# board_0_5v.net
KiCad netlist of a schematic drawn in EAGLE
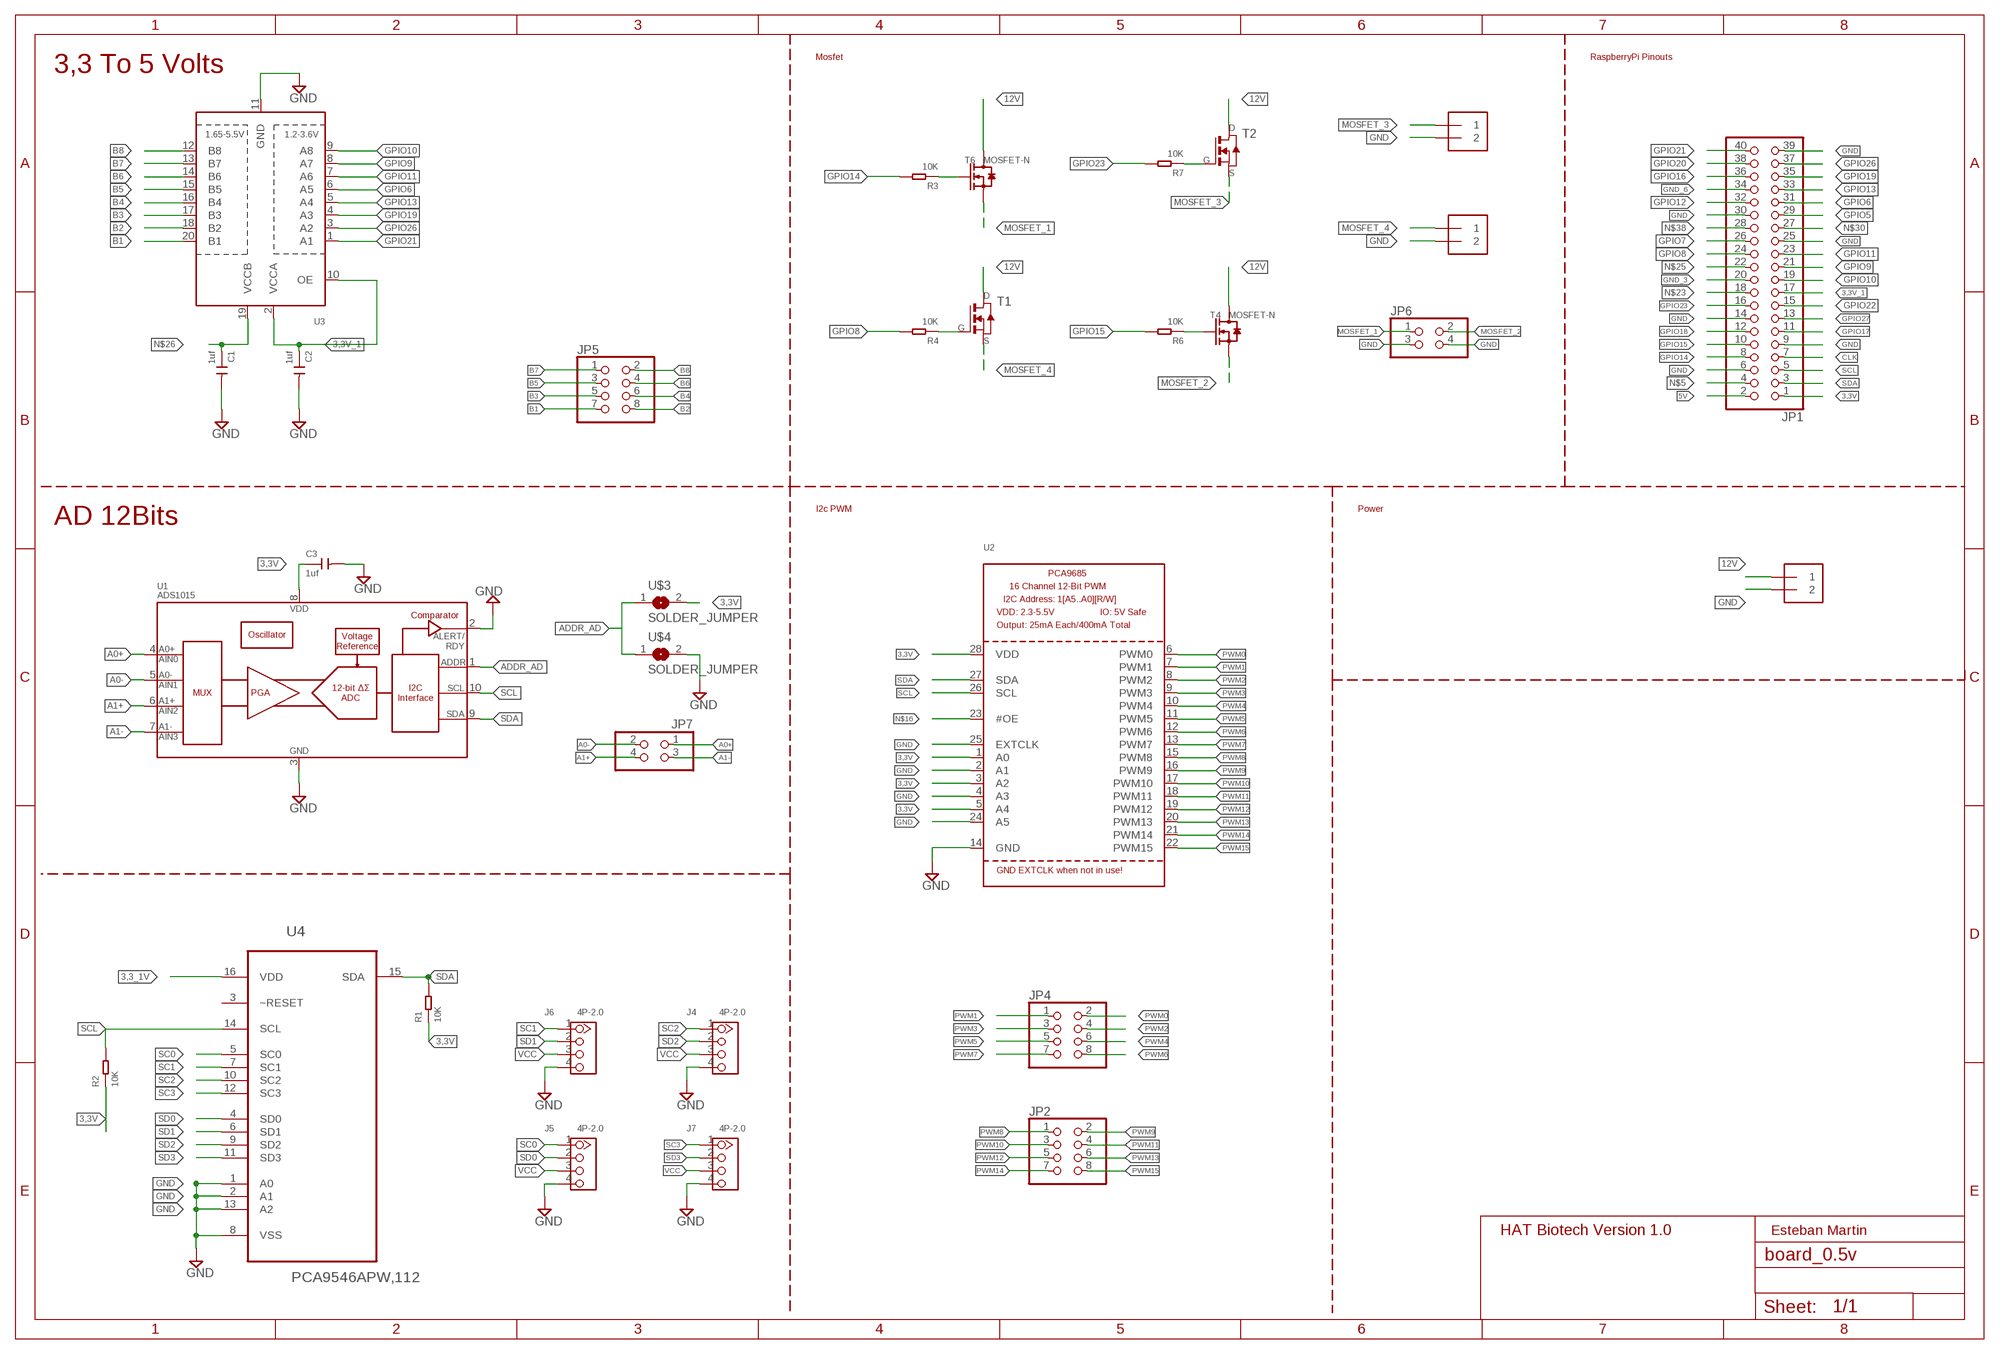
[diagram p0: schematic, sheet 1]

(export (version "E")
  (design (tool "Eeschema 10.0.6"))
  (components
    (comp (ref "C1")
      (value "1uf")
      (footprint "eagle-import:C0805")
      (fields (field (name "MPN") "CC0805KKX7R8BB105"))
      (libsource (lib "eagle-import") (part "CERAMIC-1UF-25V-10%-X7R(0805)"))
    )
    (comp (ref "C2")
      (value "1uf")
      (footprint "eagle-import:C0805")
      (fields (field (name "MPN") "CC0805KKX7R8BB105"))
      (libsource (lib "eagle-import") (part "CERAMIC-1UF-25V-10%-X7R(0805)"))
    )
    (comp (ref "C3")
      (value "1uf")
      (footprint "eagle-import:C0805")
      (fields (field (name "MPN") "CC0805KKX7R8BB105"))
      (libsource (lib "eagle-import") (part "CERAMIC-1UF-25V-10%-X7R(0805)"))
    )
    (comp (ref "J1")
      (value "1X2-3.5MM")
      (footprint "eagle-import:1X2-3.5MM")
      (libsource (lib "eagle-import") (part "1X2-3.5MM"))
    )
    (comp (ref "J2")
      (value "1X2-3.5MM")
      (footprint "eagle-import:1X2-3.5MM")
      (libsource (lib "eagle-import") (part "1X2-3.5MM"))
    )
    (comp (ref "J3")
      (value "1X2-3.5MM")
      (footprint "eagle-import:1X2-3.5MM")
      (libsource (lib "eagle-import") (part "1X2-3.5MM"))
    )
    (comp (ref "J4")
      (value "4P-2.0")
      (footprint "eagle-import:HW4-2.0")
      (libsource (lib "eagle-import") (part "GROVE-CONNECTOR-DIP(4P-2.0)"))
    )
    (comp (ref "J5")
      (value "4P-2.0")
      (footprint "eagle-import:HW4-2.0")
      (libsource (lib "eagle-import") (part "GROVE-CONNECTOR-DIP(4P-2.0)"))
    )
    (comp (ref "J6")
      (value "4P-2.0")
      (footprint "eagle-import:HW4-2.0")
      (libsource (lib "eagle-import") (part "GROVE-CONNECTOR-DIP(4P-2.0)"))
    )
    (comp (ref "J7")
      (value "4P-2.0")
      (footprint "eagle-import:HW4-2.0")
      (libsource (lib "eagle-import") (part "GROVE-CONNECTOR-DIP(4P-2.0)"))
    )
    (comp (ref "JP1")
      (value "PINHD-2X20")
      (footprint "eagle-import:2X20")
      (libsource (lib "eagle-import") (part "PINHD-2X20"))
    )
    (comp (ref "JP2")
      (value "PINHD-2X4")
      (footprint "eagle-import:2X04")
      (libsource (lib "eagle-import") (part "PINHD-2X4"))
    )
    (comp (ref "JP4")
      (value "PINHD-2X4")
      (footprint "eagle-import:2X04")
      (libsource (lib "eagle-import") (part "PINHD-2X4"))
    )
    (comp (ref "JP5")
      (value "PINHD-2X4")
      (footprint "eagle-import:2X04")
      (libsource (lib "eagle-import") (part "PINHD-2X4"))
    )
    (comp (ref "JP6")
      (value "PINHD-2X2")
      (footprint "eagle-import:2X02")
      (libsource (lib "eagle-import") (part "PINHD-2X2"))
    )
    (comp (ref "JP7")
      (value "PINHD-2X2")
      (footprint "eagle-import:2X02")
      (libsource (lib "eagle-import") (part "PINHD-2X2"))
    )
    (comp (ref "R1")
      (value "10K")
      (footprint "eagle-import:R0805")
      (fields (field (name "MPN") "RC0805FR-0710KL"))
      (libsource (lib "eagle-import") (part "SMD-RES-10K-1%-1/8W(0805)"))
    )
    (comp (ref "R2")
      (value "10K")
      (footprint "eagle-import:R0805")
      (fields (field (name "MPN") "RC0805FR-0710KL"))
      (libsource (lib "eagle-import") (part "SMD-RES-10K-1%-1/8W(0805)"))
    )
    (comp (ref "R3")
      (value "10K")
      (footprint "eagle-import:R0805")
      (fields (field (name "MPN") "RC0805FR-0710KL"))
      (libsource (lib "eagle-import") (part "SMD-RES-10K-1%-1/8W(0805)"))
    )
    (comp (ref "R4")
      (value "10K")
      (footprint "eagle-import:R0805")
      (fields (field (name "MPN") "RC0805FR-0710KL"))
      (libsource (lib "eagle-import") (part "SMD-RES-10K-1%-1/8W(0805)"))
    )
    (comp (ref "R6")
      (value "10K")
      (footprint "eagle-import:R0805")
      (fields (field (name "MPN") "RC0805FR-0710KL"))
      (libsource (lib "eagle-import") (part "SMD-RES-10K-1%-1/8W(0805)"))
    )
    (comp (ref "R7")
      (value "10K")
      (footprint "eagle-import:R0805")
      (fields (field (name "MPN") "RC0805FR-0710KL"))
      (libsource (lib "eagle-import") (part "SMD-RES-10K-1%-1/8W(0805)"))
    )
    (comp (ref "T1")
      (value "NMOSFETTO252")
      (footprint "eagle-import:TO252")
      (libsource (lib "eagle-import") (part "NMOSFETTO252"))
    )
    (comp (ref "T2")
      (value "NMOSFETTO252")
      (footprint "eagle-import:TO252")
      (libsource (lib "eagle-import") (part "NMOSFETTO252"))
    )
    (comp (ref "T4")
      (value "MOSFET-N")
      (footprint "eagle-import:SOT-23")
      (libsource (lib "eagle-import") (part "MOSFET-N"))
    )
    (comp (ref "T6")
      (value "MOSFET-N")
      (footprint "eagle-import:SOT-23")
      (libsource (lib "eagle-import") (part "MOSFET-N"))
    )
    (comp (ref "U$3")
      (value "SOLDER_JUMPER")
      (footprint "eagle-import:SJFAB")
      (libsource (lib "eagle-import") (part "SOLDER_JUMPER"))
    )
    (comp (ref "U$4")
      (value "SOLDER_JUMPER")
      (footprint "eagle-import:SJFAB")
      (libsource (lib "eagle-import") (part "SOLDER_JUMPER"))
    )
    (comp (ref "U1")
      (value "ADS1015")
      (footprint "eagle-import:MSOP10")
      (libsource (lib "eagle-import") (part "ADS1015"))
    )
    (comp (ref "U2")
      (value "PCA9685")
      (footprint "eagle-import:TSSOP28")
      (libsource (lib "eagle-import") (part "PCA9685"))
    )
    (comp (ref "U3")
      (value "TXB0108PWR")
      (footprint "eagle-import:TSSOP20")
      (libsource (lib "eagle-import") (part "TXB0108PWR"))
    )
    (comp (ref "U4")
      (value "PCA9546APW,112")
      (footprint "eagle-import:SOP65P640X110-16N")
      (libsource (lib "eagle-import") (part "PCA9546APW,112"))
    )
  )
  (nets
    (net (code "1") (name "3,3V") (class "Default")
      (node (ref "C3") (pin "1") (pinfunction "1_1") (pintype "passive"))
      (node (ref "JP1") (pin "1") (pinfunction "1_1") (pintype "passive"))
      (node (ref "R1") (pin "1") (pinfunction "1_1") (pintype "passive"))
      (node (ref "R2") (pin "1") (pinfunction "1_1") (pintype "passive"))
      (node (ref "U$3") (pin "2") (pinfunction "2_2") (pintype "passive"))
      (node (ref "U1") (pin "8") (pinfunction "VDD_8") (pintype "bidirectional"))
      (node (ref "U2") (pin "1") (pinfunction "A0_1") (pintype "bidirectional"))
      (node (ref "U2") (pin "28") (pinfunction "VDD_28") (pintype "power_in"))
      (node (ref "U2") (pin "3") (pinfunction "A2_3") (pintype "bidirectional"))
      (node (ref "U2") (pin "5") (pinfunction "A4_5") (pintype "bidirectional"))
    )
    (net (code "2") (name "3,3V_1") (class "Default")
      (node (ref "C2") (pin "1") (pinfunction "1_1") (pintype "passive"))
      (node (ref "JP1") (pin "17") (pinfunction "17_17") (pintype "passive"))
      (node (ref "U3") (pin "10") (pinfunction "OE_10") (pintype "bidirectional"))
      (node (ref "U3") (pin "2") (pinfunction "VCCA_2") (pintype "bidirectional"))
    )
    (net (code "3") (name "3,3_1V") (class "Default")
      (node (ref "U4") (pin "16") (pinfunction "VDD_16") (pintype "power_in"))
    )
    (net (code "4") (name "5V") (class "Default")
      (node (ref "JP1") (pin "2") (pinfunction "2_2") (pintype "passive"))
    )
    (net (code "5") (name "12V") (class "Default")
      (node (ref "J2") (pin "1") (pinfunction "1_1") (pintype "passive"))
      (node (ref "T1") (pin "3") (pinfunction "D_3") (pintype "passive"))
      (node (ref "T2") (pin "3") (pinfunction "D_3") (pintype "passive"))
      (node (ref "T4") (pin "3") (pinfunction "D_3") (pintype "passive"))
      (node (ref "T6") (pin "3") (pinfunction "D_3") (pintype "passive"))
    )
    (net (code "6") (name "A0+") (class "Default")
      (node (ref "JP7") (pin "1") (pinfunction "1_1") (pintype "passive"))
      (node (ref "U1") (pin "4") (pinfunction "AIN0_4") (pintype "bidirectional"))
    )
    (net (code "7") (name "A0-") (class "Default")
      (node (ref "JP7") (pin "2") (pinfunction "2_2") (pintype "passive"))
      (node (ref "U1") (pin "5") (pinfunction "AIN1_5") (pintype "bidirectional"))
    )
    (net (code "8") (name "A1+") (class "Default")
      (node (ref "JP7") (pin "4") (pinfunction "4_4") (pintype "passive"))
      (node (ref "U1") (pin "6") (pinfunction "AIN2_6") (pintype "bidirectional"))
    )
    (net (code "9") (name "A1-") (class "Default")
      (node (ref "JP7") (pin "3") (pinfunction "3_3") (pintype "passive"))
      (node (ref "U1") (pin "7") (pinfunction "AIN3_7") (pintype "bidirectional"))
    )
    (net (code "10") (name "ADDR_AD") (class "Default")
      (node (ref "U$3") (pin "1") (pinfunction "1_1") (pintype "passive"))
      (node (ref "U$4") (pin "1") (pinfunction "1_1") (pintype "passive"))
      (node (ref "U1") (pin "1") (pinfunction "ADDR_1") (pintype "bidirectional"))
    )
    (net (code "11") (name "B1") (class "Default")
      (node (ref "JP5") (pin "7") (pinfunction "7_7") (pintype "passive"))
      (node (ref "U3") (pin "20") (pinfunction "B1_20") (pintype "bidirectional"))
    )
    (net (code "12") (name "B2") (class "Default")
      (node (ref "JP5") (pin "8") (pinfunction "8_8") (pintype "passive"))
      (node (ref "U3") (pin "18") (pinfunction "B2_18") (pintype "bidirectional"))
    )
    (net (code "13") (name "B3") (class "Default")
      (node (ref "JP5") (pin "5") (pinfunction "5_5") (pintype "passive"))
      (node (ref "U3") (pin "17") (pinfunction "B3_17") (pintype "bidirectional"))
    )
    (net (code "14") (name "B4") (class "Default")
      (node (ref "JP5") (pin "6") (pinfunction "6_6") (pintype "passive"))
      (node (ref "U3") (pin "16") (pinfunction "B4_16") (pintype "bidirectional"))
    )
    (net (code "15") (name "B5") (class "Default")
      (node (ref "JP5") (pin "3") (pinfunction "3_3") (pintype "passive"))
      (node (ref "U3") (pin "15") (pinfunction "B5_15") (pintype "bidirectional"))
    )
    (net (code "16") (name "B6") (class "Default")
      (node (ref "JP5") (pin "4") (pinfunction "4_4") (pintype "passive"))
      (node (ref "U3") (pin "14") (pinfunction "B6_14") (pintype "bidirectional"))
    )
    (net (code "17") (name "B7") (class "Default")
      (node (ref "JP5") (pin "1") (pinfunction "1_1") (pintype "passive"))
      (node (ref "U3") (pin "13") (pinfunction "B7_13") (pintype "bidirectional"))
    )
    (net (code "18") (name "B8") (class "Default")
      (node (ref "JP5") (pin "2") (pinfunction "2_2") (pintype "passive"))
      (node (ref "U3") (pin "12") (pinfunction "B8_12") (pintype "bidirectional"))
    )
    (net (code "19") (name "CLK") (class "Default")
      (node (ref "JP1") (pin "7") (pinfunction "7_7") (pintype "passive"))
    )
    (net (code "20") (name "GND") (class "Default")
      (node (ref "C1") (pin "2") (pinfunction "2_2") (pintype "passive"))
      (node (ref "C2") (pin "2") (pinfunction "2_2") (pintype "passive"))
      (node (ref "C3") (pin "2") (pinfunction "2_2") (pintype "passive"))
      (node (ref "J1") (pin "2") (pinfunction "2_2") (pintype "passive"))
      (node (ref "J2") (pin "2") (pinfunction "2_2") (pintype "passive"))
      (node (ref "J3") (pin "2") (pinfunction "2_2") (pintype "passive"))
      (node (ref "J4") (pin "4") (pinfunction "4_4") (pintype "bidirectional"))
      (node (ref "J5") (pin "4") (pinfunction "4_4") (pintype "bidirectional"))
      (node (ref "J6") (pin "4") (pinfunction "4_4") (pintype "bidirectional"))
      (node (ref "J7") (pin "4") (pinfunction "4_4") (pintype "bidirectional"))
      (node (ref "JP1") (pin "14") (pinfunction "14_14") (pintype "passive"))
      (node (ref "JP1") (pin "25") (pinfunction "25_25") (pintype "passive"))
      (node (ref "JP1") (pin "30") (pinfunction "30_30") (pintype "passive"))
      (node (ref "JP1") (pin "39") (pinfunction "39_39") (pintype "passive"))
      (node (ref "JP1") (pin "6") (pinfunction "6_6") (pintype "passive"))
      (node (ref "JP1") (pin "9") (pinfunction "9_9") (pintype "passive"))
      (node (ref "JP6") (pin "3") (pinfunction "3_3") (pintype "passive"))
      (node (ref "JP6") (pin "4") (pinfunction "4_4") (pintype "passive"))
      (node (ref "U$4") (pin "2") (pinfunction "2_2") (pintype "passive"))
      (node (ref "U1") (pin "2") (pinfunction "ALERT/RDY_2") (pintype "bidirectional"))
      (node (ref "U1") (pin "3") (pinfunction "VSS_3") (pintype "bidirectional"))
      (node (ref "U2") (pin "14") (pinfunction "GND_14") (pintype "power_in"))
      (node (ref "U2") (pin "2") (pinfunction "A1_2") (pintype "bidirectional"))
      (node (ref "U2") (pin "24") (pinfunction "A5_24") (pintype "bidirectional"))
      (node (ref "U2") (pin "25") (pinfunction "EXTCLK_25") (pintype "input"))
      (node (ref "U2") (pin "4") (pinfunction "A3_4") (pintype "bidirectional"))
      (node (ref "U3") (pin "11") (pinfunction "GND_11") (pintype "bidirectional"))
      (node (ref "U4") (pin "1") (pinfunction "A0_1") (pintype "input"))
      (node (ref "U4") (pin "13") (pinfunction "A2_13") (pintype "input"))
      (node (ref "U4") (pin "2") (pinfunction "A1_2") (pintype "input"))
      (node (ref "U4") (pin "8") (pinfunction "VSS_8") (pintype "passive"))
    )
    (net (code "21") (name "GND_3") (class "Default")
      (node (ref "JP1") (pin "20") (pinfunction "20_20") (pintype "passive"))
    )
    (net (code "22") (name "GND_6") (class "Default")
      (node (ref "JP1") (pin "34") (pinfunction "34_34") (pintype "passive"))
    )
    (net (code "23") (name "GPIO5") (class "Default")
      (node (ref "JP1") (pin "29") (pinfunction "29_29") (pintype "passive"))
    )
    (net (code "24") (name "GPIO6") (class "Default")
      (node (ref "JP1") (pin "31") (pinfunction "31_31") (pintype "passive"))
      (node (ref "U3") (pin "6") (pinfunction "A5_6") (pintype "bidirectional"))
    )
    (net (code "25") (name "GPIO7") (class "Default")
      (node (ref "JP1") (pin "26") (pinfunction "26_26") (pintype "passive"))
    )
    (net (code "26") (name "GPIO8") (class "Default")
      (node (ref "JP1") (pin "24") (pinfunction "24_24") (pintype "passive"))
      (node (ref "R4") (pin "2") (pinfunction "2_2") (pintype "passive"))
    )
    (net (code "27") (name "GPIO9") (class "Default")
      (node (ref "JP1") (pin "21") (pinfunction "21_21") (pintype "passive"))
      (node (ref "U3") (pin "8") (pinfunction "A7_8") (pintype "bidirectional"))
    )
    (net (code "28") (name "GPIO10") (class "Default")
      (node (ref "JP1") (pin "19") (pinfunction "19_19") (pintype "passive"))
      (node (ref "U3") (pin "9") (pinfunction "A8_9") (pintype "bidirectional"))
    )
    (net (code "29") (name "GPIO11") (class "Default")
      (node (ref "JP1") (pin "23") (pinfunction "23_23") (pintype "passive"))
      (node (ref "U3") (pin "7") (pinfunction "A6_7") (pintype "bidirectional"))
    )
    (net (code "30") (name "GPIO12") (class "Default")
      (node (ref "JP1") (pin "32") (pinfunction "32_32") (pintype "passive"))
    )
    (net (code "31") (name "GPIO13") (class "Default")
      (node (ref "JP1") (pin "33") (pinfunction "33_33") (pintype "passive"))
      (node (ref "U3") (pin "5") (pinfunction "A4_5") (pintype "bidirectional"))
    )
    (net (code "32") (name "GPIO14") (class "Default")
      (node (ref "JP1") (pin "8") (pinfunction "8_8") (pintype "passive"))
      (node (ref "R3") (pin "2") (pinfunction "2_2") (pintype "passive"))
    )
    (net (code "33") (name "GPIO15") (class "Default")
      (node (ref "JP1") (pin "10") (pinfunction "10_10") (pintype "passive"))
      (node (ref "R6") (pin "2") (pinfunction "2_2") (pintype "passive"))
    )
    (net (code "34") (name "GPIO16") (class "Default")
      (node (ref "JP1") (pin "36") (pinfunction "36_36") (pintype "passive"))
    )
    (net (code "35") (name "GPIO17") (class "Default")
      (node (ref "JP1") (pin "11") (pinfunction "11_11") (pintype "passive"))
    )
    (net (code "36") (name "GPIO18") (class "Default")
      (node (ref "JP1") (pin "12") (pinfunction "12_12") (pintype "passive"))
    )
    (net (code "37") (name "GPIO19") (class "Default")
      (node (ref "JP1") (pin "35") (pinfunction "35_35") (pintype "passive"))
      (node (ref "U3") (pin "4") (pinfunction "A3_4") (pintype "bidirectional"))
    )
    (net (code "38") (name "GPIO20") (class "Default")
      (node (ref "JP1") (pin "38") (pinfunction "38_38") (pintype "passive"))
    )
    (net (code "39") (name "GPIO21") (class "Default")
      (node (ref "JP1") (pin "40") (pinfunction "40_40") (pintype "passive"))
      (node (ref "U3") (pin "1") (pinfunction "A1_1") (pintype "bidirectional"))
    )
    (net (code "40") (name "GPIO22") (class "Default")
      (node (ref "JP1") (pin "15") (pinfunction "15_15") (pintype "passive"))
    )
    (net (code "41") (name "GPIO23") (class "Default")
      (node (ref "JP1") (pin "16") (pinfunction "16_16") (pintype "passive"))
      (node (ref "R7") (pin "2") (pinfunction "2_2") (pintype "passive"))
    )
    (net (code "42") (name "GPIO26") (class "Default")
      (node (ref "JP1") (pin "37") (pinfunction "37_37") (pintype "passive"))
      (node (ref "U3") (pin "3") (pinfunction "A2_3") (pintype "bidirectional"))
    )
    (net (code "43") (name "GPIO27") (class "Default")
      (node (ref "JP1") (pin "13") (pinfunction "13_13") (pintype "passive"))
    )
    (net (code "44") (name "MOSFET_1") (class "Default")
      (node (ref "JP6") (pin "1") (pinfunction "1_1") (pintype "passive"))
      (node (ref "T6") (pin "2") (pinfunction "S_2") (pintype "passive"))
    )
    (net (code "45") (name "MOSFET_2") (class "Default")
      (node (ref "JP6") (pin "2") (pinfunction "2_2") (pintype "passive"))
      (node (ref "T4") (pin "2") (pinfunction "S_2") (pintype "passive"))
    )
    (net (code "46") (name "MOSFET_3") (class "Default")
      (node (ref "J1") (pin "1") (pinfunction "1_1") (pintype "passive"))
      (node (ref "T2") (pin "2") (pinfunction "S_2") (pintype "passive"))
    )
    (net (code "47") (name "MOSFET_4") (class "Default")
      (node (ref "J3") (pin "1") (pinfunction "1_1") (pintype "passive"))
      (node (ref "T1") (pin "2") (pinfunction "S_2") (pintype "passive"))
    )
    (net (code "48") (name "N$5") (class "Default")
      (node (ref "JP1") (pin "4") (pinfunction "4_4") (pintype "passive"))
    )
    (net (code "49") (name "N$16") (class "Default")
      (node (ref "U2") (pin "23") (pinfunction "#OE_23") (pintype "input"))
    )
    (net (code "50") (name "N$23") (class "Default")
      (node (ref "JP1") (pin "18") (pinfunction "18_18") (pintype "passive"))
    )
    (net (code "51") (name "N$25") (class "Default")
      (node (ref "JP1") (pin "22") (pinfunction "22_22") (pintype "passive"))
    )
    (net (code "52") (name "N$26") (class "Default")
      (node (ref "C1") (pin "1") (pinfunction "1_1") (pintype "passive"))
      (node (ref "U3") (pin "19") (pinfunction "VCCB_19") (pintype "bidirectional"))
    )
    (net (code "53") (name "N$30") (class "Default")
      (node (ref "JP1") (pin "27") (pinfunction "27_27") (pintype "passive"))
    )
    (net (code "54") (name "N$38") (class "Default")
      (node (ref "JP1") (pin "28") (pinfunction "28_28") (pintype "passive"))
    )
    (net (code "55") (name "Net-(T1-G)") (class "Default")
      (node (ref "R4") (pin "1") (pinfunction "1_1") (pintype "passive"))
      (node (ref "T1") (pin "1") (pinfunction "G_1") (pintype "passive"))
    )
    (net (code "56") (name "Net-(T2-G)") (class "Default")
      (node (ref "R7") (pin "1") (pinfunction "1_1") (pintype "passive"))
      (node (ref "T2") (pin "1") (pinfunction "G_1") (pintype "passive"))
    )
    (net (code "57") (name "Net-(T4-G)") (class "Default")
      (node (ref "R6") (pin "1") (pinfunction "1_1") (pintype "passive"))
      (node (ref "T4") (pin "1") (pinfunction "G_1") (pintype "passive"))
    )
    (net (code "58") (name "Net-(T6-G)") (class "Default")
      (node (ref "R3") (pin "1") (pinfunction "1_1") (pintype "passive"))
      (node (ref "T6") (pin "1") (pinfunction "G_1") (pintype "passive"))
    )
    (net (code "59") (name "PWM0") (class "Default")
      (node (ref "JP4") (pin "2") (pinfunction "2_2") (pintype "passive"))
      (node (ref "U2") (pin "6") (pinfunction "PWM0_6") (pintype "output"))
    )
    (net (code "60") (name "PWM1") (class "Default")
      (node (ref "JP4") (pin "1") (pinfunction "1_1") (pintype "passive"))
      (node (ref "U2") (pin "7") (pinfunction "PWM1_7") (pintype "output"))
    )
    (net (code "61") (name "PWM2") (class "Default")
      (node (ref "JP4") (pin "4") (pinfunction "4_4") (pintype "passive"))
      (node (ref "U2") (pin "8") (pinfunction "PWM2_8") (pintype "output"))
    )
    (net (code "62") (name "PWM3") (class "Default")
      (node (ref "JP4") (pin "3") (pinfunction "3_3") (pintype "passive"))
      (node (ref "U2") (pin "9") (pinfunction "PWM3_9") (pintype "output"))
    )
    (net (code "63") (name "PWM4") (class "Default")
      (node (ref "JP4") (pin "6") (pinfunction "6_6") (pintype "passive"))
      (node (ref "U2") (pin "10") (pinfunction "PWM4_10") (pintype "output"))
    )
    (net (code "64") (name "PWM5") (class "Default")
      (node (ref "JP4") (pin "5") (pinfunction "5_5") (pintype "passive"))
      (node (ref "U2") (pin "11") (pinfunction "PWM5_11") (pintype "output"))
    )
    (net (code "65") (name "PWM6") (class "Default")
      (node (ref "JP4") (pin "8") (pinfunction "8_8") (pintype "passive"))
      (node (ref "U2") (pin "12") (pinfunction "PWM6_12") (pintype "output"))
    )
    (net (code "66") (name "PWM7") (class "Default")
      (node (ref "JP4") (pin "7") (pinfunction "7_7") (pintype "passive"))
      (node (ref "U2") (pin "13") (pinfunction "PWM7_13") (pintype "output"))
    )
    (net (code "67") (name "PWM8") (class "Default")
      (node (ref "JP2") (pin "1") (pinfunction "1_1") (pintype "passive"))
      (node (ref "U2") (pin "15") (pinfunction "PWM8_15") (pintype "output"))
    )
    (net (code "68") (name "PWM9") (class "Default")
      (node (ref "JP2") (pin "2") (pinfunction "2_2") (pintype "passive"))
      (node (ref "U2") (pin "16") (pinfunction "PWM9_16") (pintype "output"))
    )
    (net (code "69") (name "PWM10") (class "Default")
      (node (ref "JP2") (pin "3") (pinfunction "3_3") (pintype "passive"))
      (node (ref "U2") (pin "17") (pinfunction "PWM10_17") (pintype "output"))
    )
    (net (code "70") (name "PWM11") (class "Default")
      (node (ref "JP2") (pin "4") (pinfunction "4_4") (pintype "passive"))
      (node (ref "U2") (pin "18") (pinfunction "PWM11_18") (pintype "output"))
    )
    (net (code "71") (name "PWM12") (class "Default")
      (node (ref "JP2") (pin "5") (pinfunction "5_5") (pintype "passive"))
      (node (ref "U2") (pin "19") (pinfunction "PWM12_19") (pintype "output"))
    )
    (net (code "72") (name "PWM13") (class "Default")
      (node (ref "JP2") (pin "6") (pinfunction "6_6") (pintype "passive"))
      (node (ref "U2") (pin "20") (pinfunction "PWM13_20") (pintype "output"))
    )
    (net (code "73") (name "PWM14") (class "Default")
      (node (ref "JP2") (pin "7") (pinfunction "7_7") (pintype "passive"))
      (node (ref "U2") (pin "21") (pinfunction "PWM14_21") (pintype "output"))
    )
    (net (code "74") (name "PWM15") (class "Default")
      (node (ref "JP2") (pin "8") (pinfunction "8_8") (pintype "passive"))
      (node (ref "U2") (pin "22") (pinfunction "PWM15_22") (pintype "output"))
    )
    (net (code "75") (name "SC0") (class "Default")
      (node (ref "J5") (pin "1") (pinfunction "1_1") (pintype "bidirectional"))
      (node (ref "U4") (pin "5") (pinfunction "SC0_5") (pintype "input"))
    )
    (net (code "76") (name "SC1") (class "Default")
      (node (ref "J6") (pin "1") (pinfunction "1_1") (pintype "bidirectional"))
      (node (ref "U4") (pin "7") (pinfunction "SC1_7") (pintype "input"))
    )
    (net (code "77") (name "SC2") (class "Default")
      (node (ref "J4") (pin "1") (pinfunction "1_1") (pintype "bidirectional"))
      (node (ref "U4") (pin "10") (pinfunction "SC2_10") (pintype "input"))
    )
    (net (code "78") (name "SC3") (class "Default")
      (node (ref "J7") (pin "1") (pinfunction "1_1") (pintype "bidirectional"))
      (node (ref "U4") (pin "12") (pinfunction "SC3_12") (pintype "input"))
    )
    (net (code "79") (name "SCL") (class "Default")
      (node (ref "JP1") (pin "5") (pinfunction "5_5") (pintype "passive"))
      (node (ref "R2") (pin "2") (pinfunction "2_2") (pintype "passive"))
      (node (ref "U1") (pin "10") (pinfunction "SCL_10") (pintype "bidirectional"))
      (node (ref "U2") (pin "26") (pinfunction "SCL_26") (pintype "bidirectional"))
      (node (ref "U4") (pin "14") (pinfunction "SCL_14") (pintype "bidirectional"))
    )
    (net (code "80") (name "SD0") (class "Default")
      (node (ref "J5") (pin "2") (pinfunction "2_2") (pintype "bidirectional"))
      (node (ref "U4") (pin "4") (pinfunction "SD0_4") (pintype "input"))
    )
    (net (code "81") (name "SD1") (class "Default")
      (node (ref "J6") (pin "2") (pinfunction "2_2") (pintype "bidirectional"))
      (node (ref "U4") (pin "6") (pinfunction "SD1_6") (pintype "input"))
    )
    (net (code "82") (name "SD2") (class "Default")
      (node (ref "J4") (pin "2") (pinfunction "2_2") (pintype "bidirectional"))
      (node (ref "U4") (pin "9") (pinfunction "SD2_9") (pintype "input"))
    )
    (net (code "83") (name "SD3") (class "Default")
      (node (ref "J7") (pin "2") (pinfunction "2_2") (pintype "bidirectional"))
      (node (ref "U4") (pin "11") (pinfunction "SD3_11") (pintype "input"))
    )
    (net (code "84") (name "SDA") (class "Default")
      (node (ref "JP1") (pin "3") (pinfunction "3_3") (pintype "passive"))
      (node (ref "R1") (pin "2") (pinfunction "2_2") (pintype "passive"))
      (node (ref "U1") (pin "9") (pinfunction "SDA_9") (pintype "bidirectional"))
      (node (ref "U2") (pin "27") (pinfunction "SDA_27") (pintype "bidirectional"))
      (node (ref "U4") (pin "15") (pinfunction "SDA_15") (pintype "bidirectional"))
    )
    (net (code "85") (name "VCC") (class "Default")
      (node (ref "J4") (pin "3") (pinfunction "3_3") (pintype "bidirectional"))
      (node (ref "J5") (pin "3") (pinfunction "3_3") (pintype "bidirectional"))
      (node (ref "J6") (pin "3") (pinfunction "3_3") (pintype "bidirectional"))
      (node (ref "J7") (pin "3") (pinfunction "3_3") (pintype "bidirectional"))
    )
    (net (code "86") (name "unconnected-(U4-~{RESET}-Pad3)") (class "Default")
      (node (ref "U4") (pin "3") (pinfunction "~{RESET}_3") (pintype "input"))
    )
  )
)
